# sens.net
KiCad netlist of a schematic drawn in EAGLE
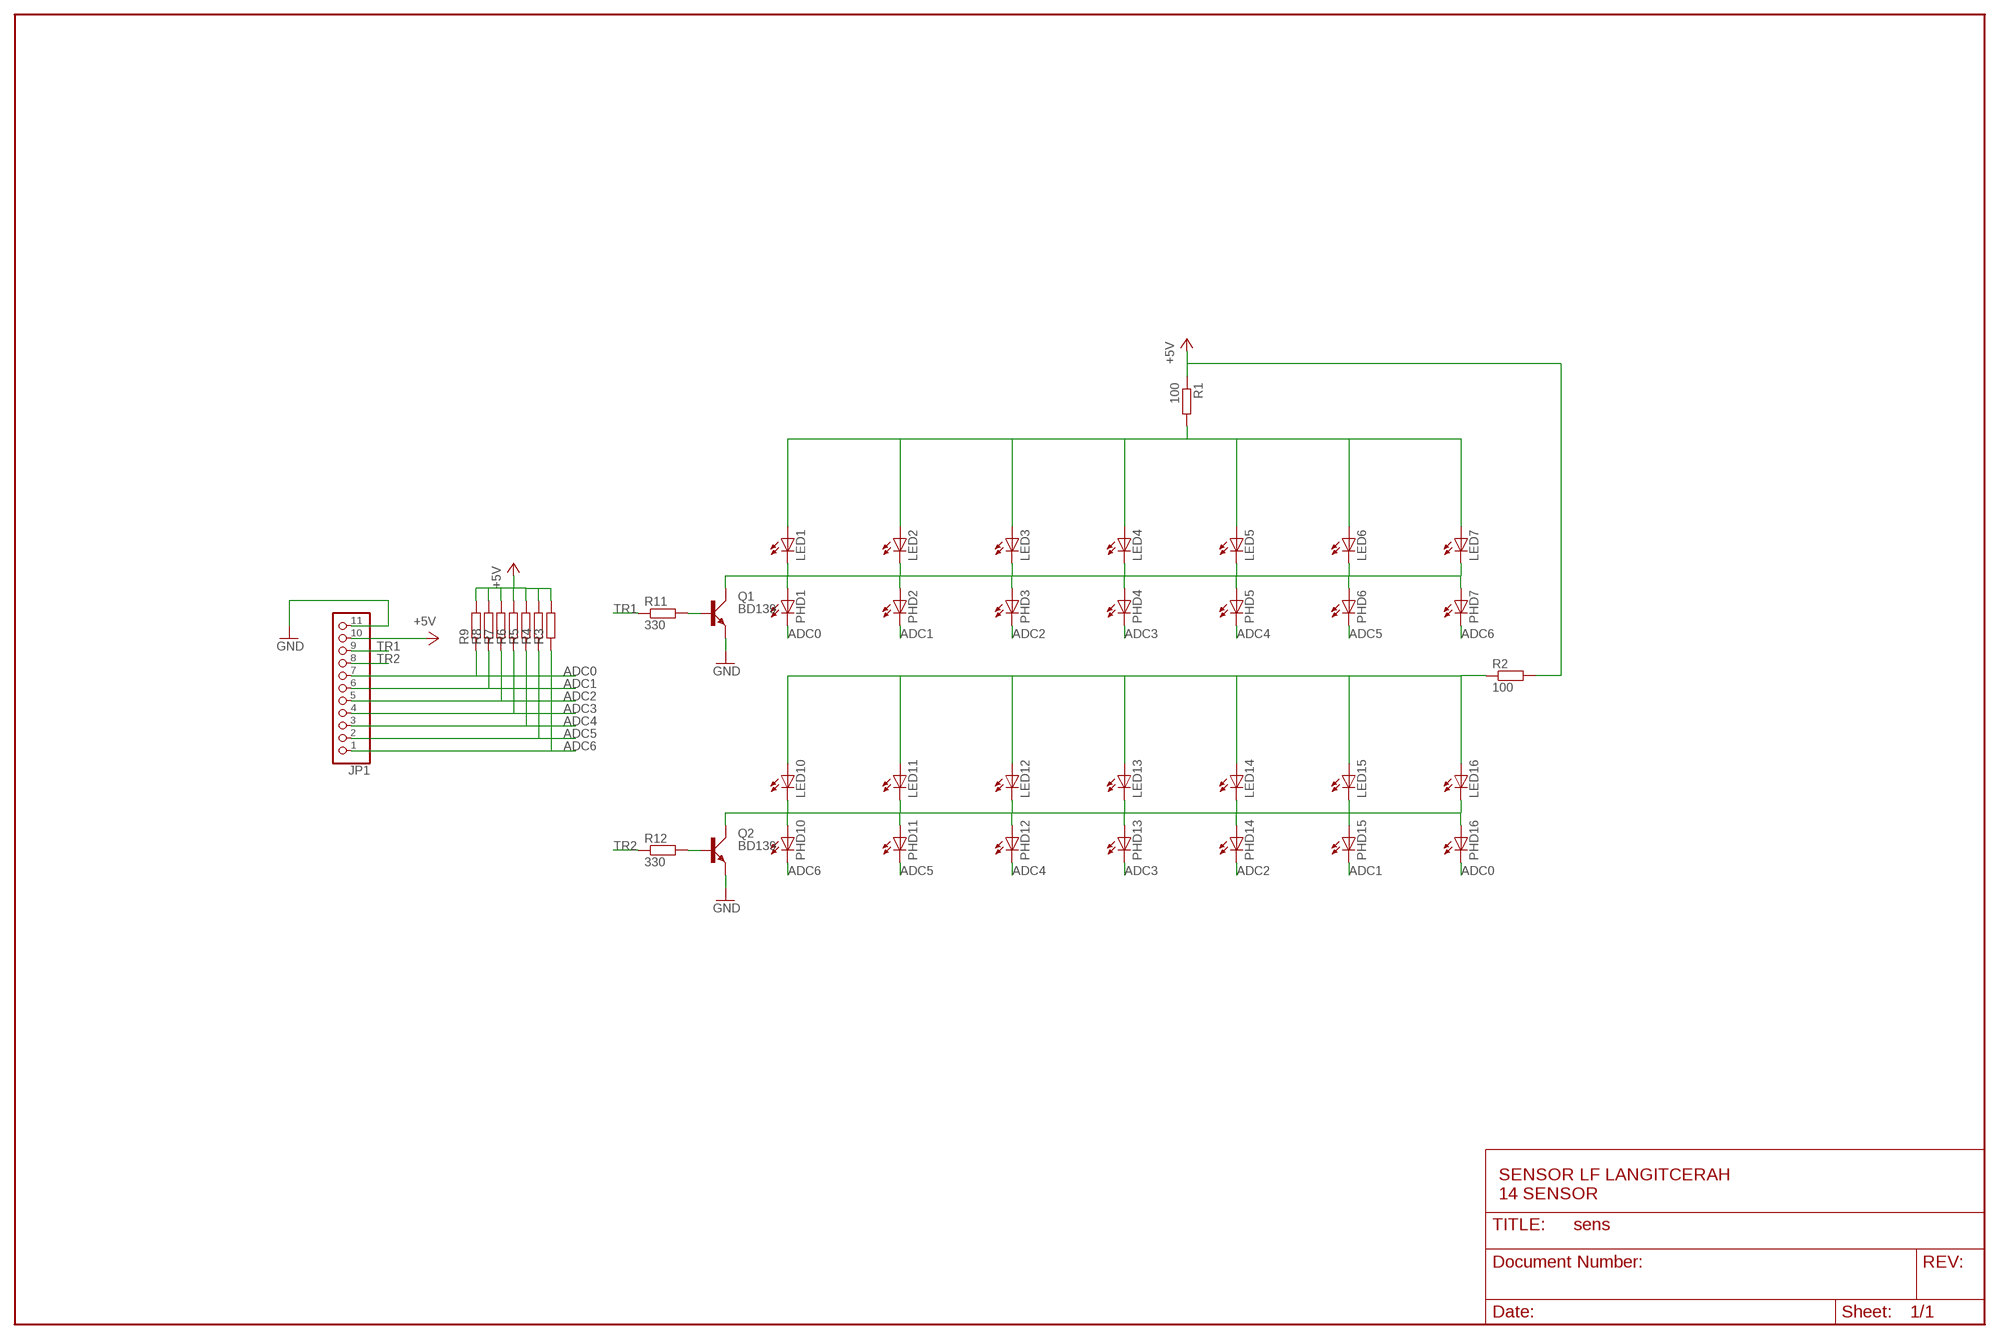
[diagram p0: schematic, sheet 1]

(export (version "E")
  (design (tool "Eeschema 10.0.6"))
  (components
    (comp (ref "JP1")
      (value "PINHD-1X11")
      (footprint "eagle-import:1X11")
      (libsource (lib "eagle-import") (part "PINHD-1X11"))
    )
    (comp (ref "LED1")
      (value "LED3MM")
      (footprint "eagle-import:LED3MM")
      (libsource (lib "eagle-import") (part "LED3MM"))
    )
    (comp (ref "LED2")
      (value "LED3MM")
      (footprint "eagle-import:LED3MM")
      (libsource (lib "eagle-import") (part "LED3MM"))
    )
    (comp (ref "LED3")
      (value "LED3MM")
      (footprint "eagle-import:LED3MM")
      (libsource (lib "eagle-import") (part "LED3MM"))
    )
    (comp (ref "LED4")
      (value "LED3MM")
      (footprint "eagle-import:LED3MM")
      (libsource (lib "eagle-import") (part "LED3MM"))
    )
    (comp (ref "LED5")
      (value "LED3MM")
      (footprint "eagle-import:LED3MM")
      (libsource (lib "eagle-import") (part "LED3MM"))
    )
    (comp (ref "LED6")
      (value "LED3MM")
      (footprint "eagle-import:LED3MM")
      (libsource (lib "eagle-import") (part "LED3MM"))
    )
    (comp (ref "LED7")
      (value "LED3MM")
      (footprint "eagle-import:LED3MM")
      (libsource (lib "eagle-import") (part "LED3MM"))
    )
    (comp (ref "LED10")
      (value "LED3MM")
      (footprint "eagle-import:LED3MM")
      (libsource (lib "eagle-import") (part "LED3MM"))
    )
    (comp (ref "LED11")
      (value "LED3MM")
      (footprint "eagle-import:LED3MM")
      (libsource (lib "eagle-import") (part "LED3MM"))
    )
    (comp (ref "LED12")
      (value "LED3MM")
      (footprint "eagle-import:LED3MM")
      (libsource (lib "eagle-import") (part "LED3MM"))
    )
    (comp (ref "LED13")
      (value "LED3MM")
      (footprint "eagle-import:LED3MM")
      (libsource (lib "eagle-import") (part "LED3MM"))
    )
    (comp (ref "LED14")
      (value "LED3MM")
      (footprint "eagle-import:LED3MM")
      (libsource (lib "eagle-import") (part "LED3MM"))
    )
    (comp (ref "LED15")
      (value "LED3MM")
      (footprint "eagle-import:LED3MM")
      (libsource (lib "eagle-import") (part "LED3MM"))
    )
    (comp (ref "LED16")
      (value "LED3MM")
      (footprint "eagle-import:LED3MM")
      (libsource (lib "eagle-import") (part "LED3MM"))
    )
    (comp (ref "PHD1")
      (value "LED3MM")
      (footprint "eagle-import:LED3MM")
      (libsource (lib "eagle-import") (part "LED3MM"))
    )
    (comp (ref "PHD2")
      (value "LED3MM")
      (footprint "eagle-import:LED3MM")
      (libsource (lib "eagle-import") (part "LED3MM"))
    )
    (comp (ref "PHD3")
      (value "LED3MM")
      (footprint "eagle-import:LED3MM")
      (libsource (lib "eagle-import") (part "LED3MM"))
    )
    (comp (ref "PHD4")
      (value "LED3MM")
      (footprint "eagle-import:LED3MM")
      (libsource (lib "eagle-import") (part "LED3MM"))
    )
    (comp (ref "PHD5")
      (value "LED3MM")
      (footprint "eagle-import:LED3MM")
      (libsource (lib "eagle-import") (part "LED3MM"))
    )
    (comp (ref "PHD6")
      (value "LED3MM")
      (footprint "eagle-import:LED3MM")
      (libsource (lib "eagle-import") (part "LED3MM"))
    )
    (comp (ref "PHD7")
      (value "LED3MM")
      (footprint "eagle-import:LED3MM")
      (libsource (lib "eagle-import") (part "LED3MM"))
    )
    (comp (ref "PHD10")
      (value "LED3MM")
      (footprint "eagle-import:LED3MM")
      (libsource (lib "eagle-import") (part "LED3MM"))
    )
    (comp (ref "PHD11")
      (value "LED3MM")
      (footprint "eagle-import:LED3MM")
      (libsource (lib "eagle-import") (part "LED3MM"))
    )
    (comp (ref "PHD12")
      (value "LED3MM")
      (footprint "eagle-import:LED3MM")
      (libsource (lib "eagle-import") (part "LED3MM"))
    )
    (comp (ref "PHD13")
      (value "LED3MM")
      (footprint "eagle-import:LED3MM")
      (libsource (lib "eagle-import") (part "LED3MM"))
    )
    (comp (ref "PHD14")
      (value "LED3MM")
      (footprint "eagle-import:LED3MM")
      (libsource (lib "eagle-import") (part "LED3MM"))
    )
    (comp (ref "PHD15")
      (value "LED3MM")
      (footprint "eagle-import:LED3MM")
      (libsource (lib "eagle-import") (part "LED3MM"))
    )
    (comp (ref "PHD16")
      (value "LED3MM")
      (footprint "eagle-import:LED3MM")
      (libsource (lib "eagle-import") (part "LED3MM"))
    )
    (comp (ref "Q1")
      (value "BD139")
      (footprint "eagle-import:TO126AV")
      (libsource (lib "eagle-import") (part "BD139"))
    )
    (comp (ref "Q2")
      (value "BD139")
      (footprint "eagle-import:TO126AV")
      (libsource (lib "eagle-import") (part "BD139"))
    )
    (comp (ref "R1")
      (value "100")
      (footprint "eagle-import:0207_10")
      (libsource (lib "eagle-import") (part "R-EU_0207/10"))
    )
    (comp (ref "R2")
      (value "100")
      (footprint "eagle-import:0207_10")
      (libsource (lib "eagle-import") (part "R-EU_0207/10"))
    )
    (comp (ref "R3")
      (value "R-EU_0207/10")
      (footprint "eagle-import:0207_10")
      (libsource (lib "eagle-import") (part "R-EU_0207/10"))
    )
    (comp (ref "R4")
      (value "R-EU_0207/10")
      (footprint "eagle-import:0207_10")
      (libsource (lib "eagle-import") (part "R-EU_0207/10"))
    )
    (comp (ref "R5")
      (value "R-EU_0207/10")
      (footprint "eagle-import:0207_10")
      (libsource (lib "eagle-import") (part "R-EU_0207/10"))
    )
    (comp (ref "R6")
      (value "R-EU_0207/10")
      (footprint "eagle-import:0207_10")
      (libsource (lib "eagle-import") (part "R-EU_0207/10"))
    )
    (comp (ref "R7")
      (value "R-EU_0207/10")
      (footprint "eagle-import:0207_10")
      (libsource (lib "eagle-import") (part "R-EU_0207/10"))
    )
    (comp (ref "R8")
      (value "R-EU_0207/10")
      (footprint "eagle-import:0207_10")
      (libsource (lib "eagle-import") (part "R-EU_0207/10"))
    )
    (comp (ref "R9")
      (value "R-EU_0207/10")
      (footprint "eagle-import:0207_10")
      (libsource (lib "eagle-import") (part "R-EU_0207/10"))
    )
    (comp (ref "R11")
      (value "330")
      (footprint "eagle-import:0207_10")
      (libsource (lib "eagle-import") (part "R-EU_0207/10"))
    )
    (comp (ref "R12")
      (value "330")
      (footprint "eagle-import:0207_10")
      (libsource (lib "eagle-import") (part "R-EU_0207/10"))
    )
  )
  (nets
    (net (code "1") (name "+5V") (class "Default")
      (node (ref "JP1") (pin "10") (pinfunction "10_10") (pintype "passive"))
      (node (ref "R1") (pin "1") (pinfunction "1_1") (pintype "passive"))
      (node (ref "R2") (pin "2") (pinfunction "2_2") (pintype "passive"))
      (node (ref "R3") (pin "2") (pinfunction "2_2") (pintype "passive"))
      (node (ref "R4") (pin "2") (pinfunction "2_2") (pintype "passive"))
      (node (ref "R5") (pin "2") (pinfunction "2_2") (pintype "passive"))
      (node (ref "R6") (pin "2") (pinfunction "2_2") (pintype "passive"))
      (node (ref "R7") (pin "2") (pinfunction "2_2") (pintype "passive"))
      (node (ref "R8") (pin "2") (pinfunction "2_2") (pintype "passive"))
      (node (ref "R9") (pin "2") (pinfunction "2_2") (pintype "passive"))
    )
    (net (code "2") (name "/ADC0") (class "Default")
      (node (ref "JP1") (pin "7") (pinfunction "7_7") (pintype "passive"))
      (node (ref "PHD1") (pin "K") (pinfunction "C_K") (pintype "passive"))
      (node (ref "PHD16") (pin "K") (pinfunction "C_K") (pintype "passive"))
      (node (ref "R9") (pin "1") (pinfunction "1_1") (pintype "passive"))
    )
    (net (code "3") (name "/ADC1") (class "Default")
      (node (ref "JP1") (pin "6") (pinfunction "6_6") (pintype "passive"))
      (node (ref "PHD15") (pin "K") (pinfunction "C_K") (pintype "passive"))
      (node (ref "PHD2") (pin "K") (pinfunction "C_K") (pintype "passive"))
      (node (ref "R8") (pin "1") (pinfunction "1_1") (pintype "passive"))
    )
    (net (code "4") (name "/ADC2") (class "Default")
      (node (ref "JP1") (pin "5") (pinfunction "5_5") (pintype "passive"))
      (node (ref "PHD14") (pin "K") (pinfunction "C_K") (pintype "passive"))
      (node (ref "PHD3") (pin "K") (pinfunction "C_K") (pintype "passive"))
      (node (ref "R7") (pin "1") (pinfunction "1_1") (pintype "passive"))
    )
    (net (code "5") (name "/ADC3") (class "Default")
      (node (ref "JP1") (pin "4") (pinfunction "4_4") (pintype "passive"))
      (node (ref "PHD13") (pin "K") (pinfunction "C_K") (pintype "passive"))
      (node (ref "PHD4") (pin "K") (pinfunction "C_K") (pintype "passive"))
      (node (ref "R6") (pin "1") (pinfunction "1_1") (pintype "passive"))
    )
    (net (code "6") (name "/ADC4") (class "Default")
      (node (ref "JP1") (pin "3") (pinfunction "3_3") (pintype "passive"))
      (node (ref "PHD12") (pin "K") (pinfunction "C_K") (pintype "passive"))
      (node (ref "PHD5") (pin "K") (pinfunction "C_K") (pintype "passive"))
      (node (ref "R5") (pin "1") (pinfunction "1_1") (pintype "passive"))
    )
    (net (code "7") (name "/ADC5") (class "Default")
      (node (ref "JP1") (pin "2") (pinfunction "2_2") (pintype "passive"))
      (node (ref "PHD11") (pin "K") (pinfunction "C_K") (pintype "passive"))
      (node (ref "PHD6") (pin "K") (pinfunction "C_K") (pintype "passive"))
      (node (ref "R4") (pin "1") (pinfunction "1_1") (pintype "passive"))
    )
    (net (code "8") (name "/ADC6") (class "Default")
      (node (ref "JP1") (pin "1") (pinfunction "1_1") (pintype "passive"))
      (node (ref "PHD10") (pin "K") (pinfunction "C_K") (pintype "passive"))
      (node (ref "PHD7") (pin "K") (pinfunction "C_K") (pintype "passive"))
      (node (ref "R3") (pin "1") (pinfunction "1_1") (pintype "passive"))
    )
    (net (code "9") (name "/TR1") (class "Default")
      (node (ref "JP1") (pin "9") (pinfunction "9_9") (pintype "passive"))
      (node (ref "R11") (pin "1") (pinfunction "1_1") (pintype "passive"))
    )
    (net (code "10") (name "/TR2") (class "Default")
      (node (ref "JP1") (pin "8") (pinfunction "8_8") (pintype "passive"))
      (node (ref "R12") (pin "1") (pinfunction "1_1") (pintype "passive"))
    )
    (net (code "11") (name "GND") (class "Default")
      (node (ref "JP1") (pin "11") (pinfunction "11_11") (pintype "passive"))
      (node (ref "Q1") (pin "E") (pinfunction "E_E") (pintype "passive"))
      (node (ref "Q2") (pin "E") (pinfunction "E_E") (pintype "passive"))
    )
    (net (code "12") (name "Net-(LED1-C)") (class "Default")
      (node (ref "LED1") (pin "K") (pinfunction "C_K") (pintype "passive"))
      (node (ref "LED2") (pin "K") (pinfunction "C_K") (pintype "passive"))
      (node (ref "LED3") (pin "K") (pinfunction "C_K") (pintype "passive"))
      (node (ref "LED4") (pin "K") (pinfunction "C_K") (pintype "passive"))
      (node (ref "LED5") (pin "K") (pinfunction "C_K") (pintype "passive"))
      (node (ref "LED6") (pin "K") (pinfunction "C_K") (pintype "passive"))
      (node (ref "LED7") (pin "K") (pinfunction "C_K") (pintype "passive"))
      (node (ref "PHD1") (pin "A") (pinfunction "A_A") (pintype "passive"))
      (node (ref "PHD2") (pin "A") (pinfunction "A_A") (pintype "passive"))
      (node (ref "PHD3") (pin "A") (pinfunction "A_A") (pintype "passive"))
      (node (ref "PHD4") (pin "A") (pinfunction "A_A") (pintype "passive"))
      (node (ref "PHD5") (pin "A") (pinfunction "A_A") (pintype "passive"))
      (node (ref "PHD6") (pin "A") (pinfunction "A_A") (pintype "passive"))
      (node (ref "PHD7") (pin "A") (pinfunction "A_A") (pintype "passive"))
      (node (ref "Q1") (pin "C") (pinfunction "C_C") (pintype "passive"))
    )
    (net (code "13") (name "Net-(LED1-PadA)") (class "Default")
      (node (ref "LED1") (pin "A") (pinfunction "A_A") (pintype "passive"))
      (node (ref "LED2") (pin "A") (pinfunction "A_A") (pintype "passive"))
      (node (ref "LED3") (pin "A") (pinfunction "A_A") (pintype "passive"))
      (node (ref "LED4") (pin "A") (pinfunction "A_A") (pintype "passive"))
      (node (ref "LED5") (pin "A") (pinfunction "A_A") (pintype "passive"))
      (node (ref "LED6") (pin "A") (pinfunction "A_A") (pintype "passive"))
      (node (ref "LED7") (pin "A") (pinfunction "A_A") (pintype "passive"))
      (node (ref "R1") (pin "2") (pinfunction "2_2") (pintype "passive"))
    )
    (net (code "14") (name "Net-(LED10-C)") (class "Default")
      (node (ref "LED10") (pin "K") (pinfunction "C_K") (pintype "passive"))
      (node (ref "LED11") (pin "K") (pinfunction "C_K") (pintype "passive"))
      (node (ref "LED12") (pin "K") (pinfunction "C_K") (pintype "passive"))
      (node (ref "LED13") (pin "K") (pinfunction "C_K") (pintype "passive"))
      (node (ref "LED14") (pin "K") (pinfunction "C_K") (pintype "passive"))
      (node (ref "LED15") (pin "K") (pinfunction "C_K") (pintype "passive"))
      (node (ref "LED16") (pin "K") (pinfunction "C_K") (pintype "passive"))
      (node (ref "PHD10") (pin "A") (pinfunction "A_A") (pintype "passive"))
      (node (ref "PHD11") (pin "A") (pinfunction "A_A") (pintype "passive"))
      (node (ref "PHD12") (pin "A") (pinfunction "A_A") (pintype "passive"))
      (node (ref "PHD13") (pin "A") (pinfunction "A_A") (pintype "passive"))
      (node (ref "PHD14") (pin "A") (pinfunction "A_A") (pintype "passive"))
      (node (ref "PHD15") (pin "A") (pinfunction "A_A") (pintype "passive"))
      (node (ref "PHD16") (pin "A") (pinfunction "A_A") (pintype "passive"))
      (node (ref "Q2") (pin "C") (pinfunction "C_C") (pintype "passive"))
    )
    (net (code "15") (name "Net-(LED10-PadA)") (class "Default")
      (node (ref "LED10") (pin "A") (pinfunction "A_A") (pintype "passive"))
      (node (ref "LED11") (pin "A") (pinfunction "A_A") (pintype "passive"))
      (node (ref "LED12") (pin "A") (pinfunction "A_A") (pintype "passive"))
      (node (ref "LED13") (pin "A") (pinfunction "A_A") (pintype "passive"))
      (node (ref "LED14") (pin "A") (pinfunction "A_A") (pintype "passive"))
      (node (ref "LED15") (pin "A") (pinfunction "A_A") (pintype "passive"))
      (node (ref "LED16") (pin "A") (pinfunction "A_A") (pintype "passive"))
      (node (ref "R2") (pin "1") (pinfunction "1_1") (pintype "passive"))
    )
    (net (code "16") (name "Net-(Q1-PadB)") (class "Default")
      (node (ref "Q1") (pin "B") (pinfunction "B_B") (pintype "passive"))
      (node (ref "R11") (pin "2") (pinfunction "2_2") (pintype "passive"))
    )
    (net (code "17") (name "Net-(Q2-PadB)") (class "Default")
      (node (ref "Q2") (pin "B") (pinfunction "B_B") (pintype "passive"))
      (node (ref "R12") (pin "2") (pinfunction "2_2") (pintype "passive"))
    )
  )
)
